# Connections.net
KiCad netlist of a schematic drawn in EAGLE
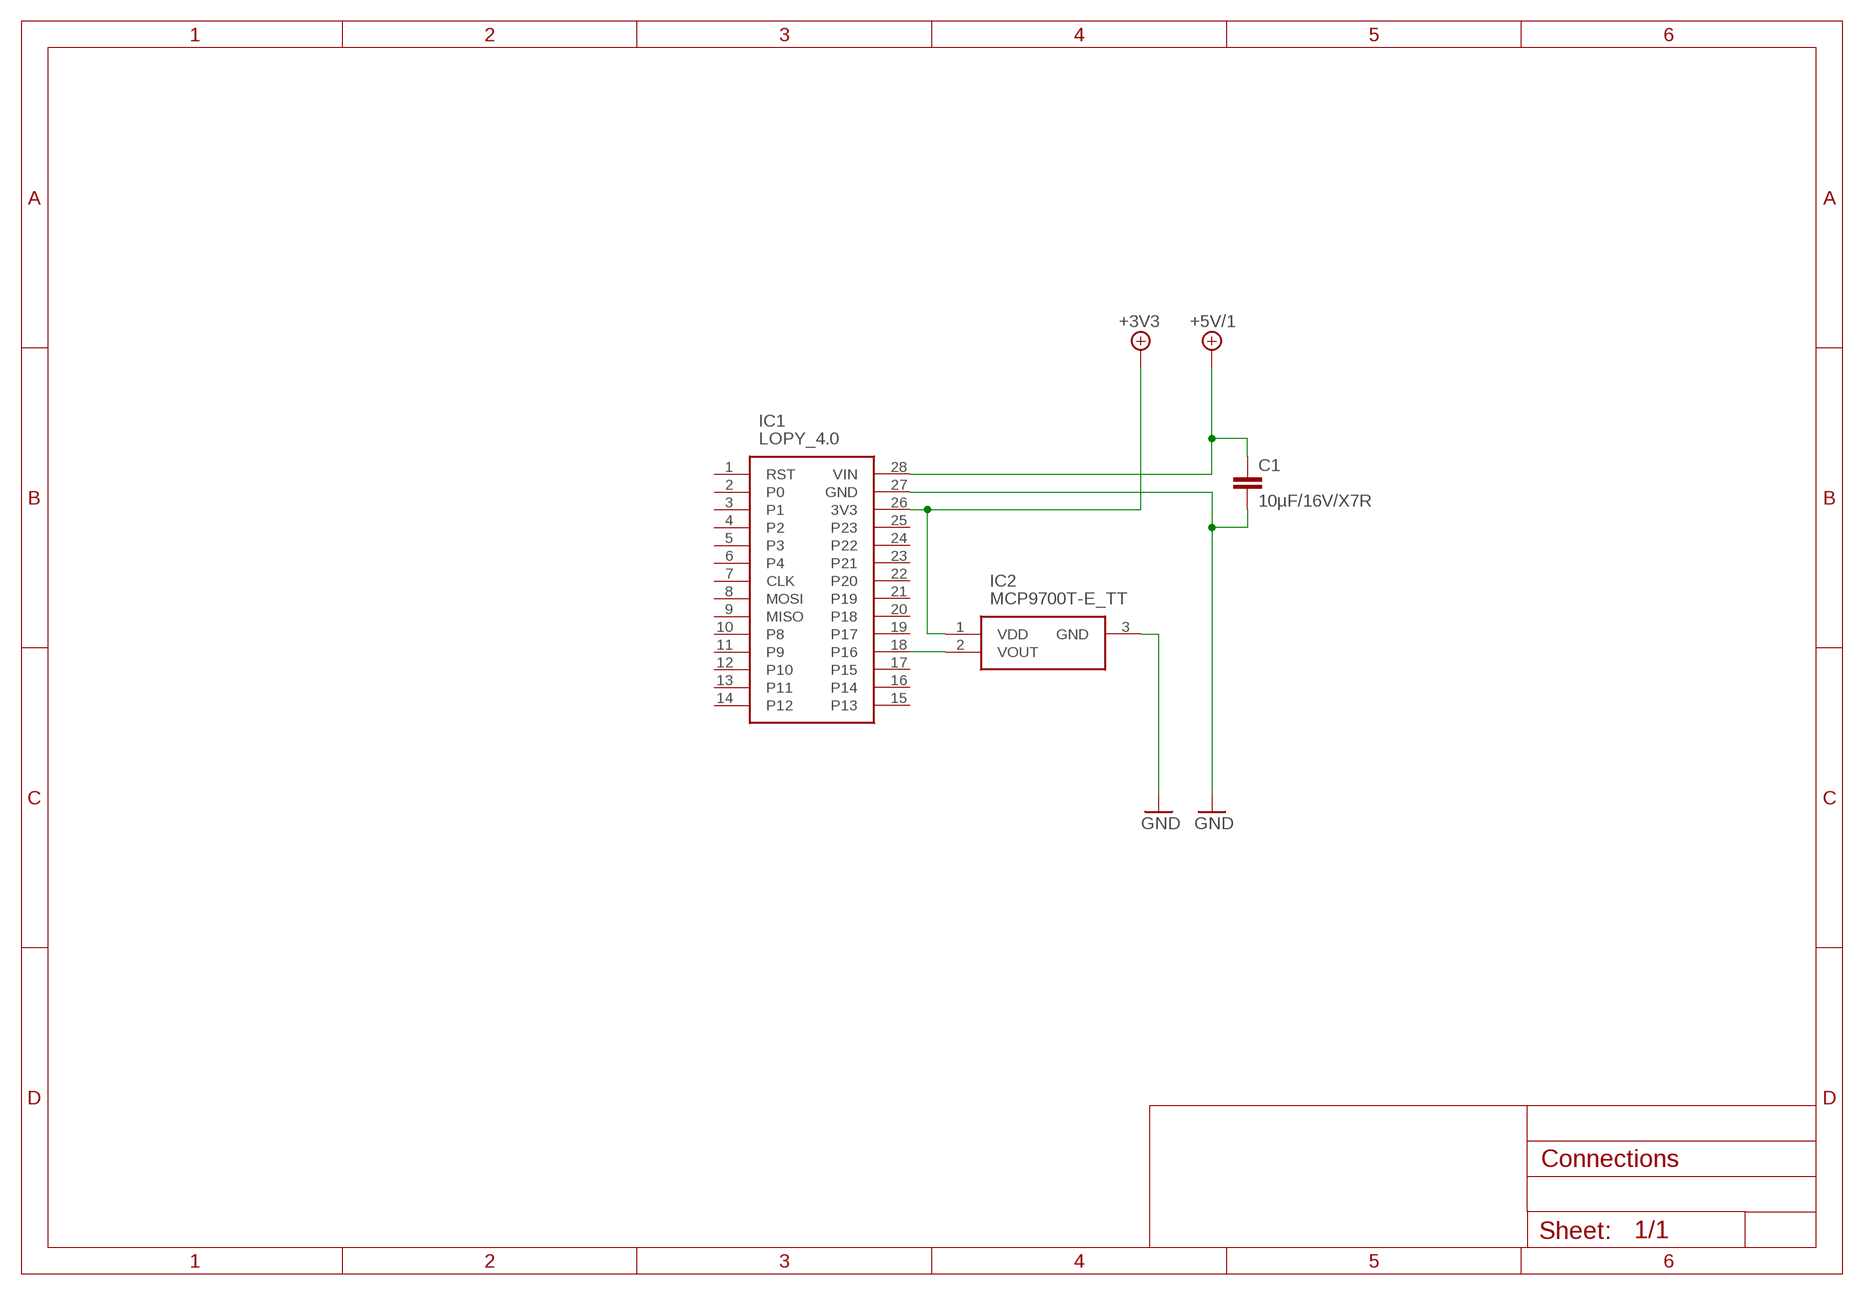
[diagram p0: schematic, sheet 1]

(export (version "E")
  (design (tool "Eeschema 10.0.6"))
  (components
    (comp (ref "C1")
      (value "10µF/16V/X7R")
      (footprint "eagle-import:C0603")
      (libsource (lib "eagle-import") (part "C-EUC0603"))
    )
    (comp (ref "IC1")
      (value "LOPY_4.0")
      (footprint "eagle-import:LOPY40")
      (fields (field (name "ARROW_PART_NUMBER") "LoPy 4.0") (field (name "MOUSER_PART_NUMBER") "365-LOPY4"))
      (libsource (lib "eagle-import") (part "LOPY_4.0"))
    )
    (comp (ref "IC2")
      (value "MCP9700T-E_TT")
      (footprint "eagle-import:SOT95P237X112-3N")
      (fields
        (field (name "ARROW_PART_NUMBER") "MCP9700T-E/TT")
        (field (name "MOUSER_PART_NUMBER") "579-MCP9700T-E/TT")
      )
      (libsource (lib "eagle-import") (part "MCP9700T-E_TT"))
    )
  )
  (nets
    (net (code "1") (name "+3V3") (class "Default")
      (node (ref "IC1") (pin "26") (pinfunction "3V3_26") (pintype "bidirectional"))
      (node (ref "IC2") (pin "1") (pinfunction "VDD_1") (pintype "bidirectional"))
    )
    (net (code "2") (name "+5V{slash}1") (class "Default")
      (node (ref "C1") (pin "1") (pinfunction "1_1") (pintype "passive"))
      (node (ref "IC1") (pin "28") (pinfunction "VIN_28") (pintype "bidirectional"))
    )
    (net (code "3") (name "GND") (class "Default")
      (node (ref "C1") (pin "2") (pinfunction "2_2") (pintype "passive"))
      (node (ref "IC1") (pin "27") (pinfunction "GND_27") (pintype "bidirectional"))
      (node (ref "IC2") (pin "3") (pinfunction "GND_3") (pintype "bidirectional"))
    )
    (net (code "4") (name "Net-(IC1-P16)") (class "Default")
      (node (ref "IC1") (pin "18") (pinfunction "P16_18") (pintype "bidirectional"))
      (node (ref "IC2") (pin "2") (pinfunction "VOUT_2") (pintype "bidirectional"))
    )
    (net (code "5") (name "unconnected-(IC1-CLK-Pad7)") (class "Default")
      (node (ref "IC1") (pin "7") (pinfunction "CLK_7") (pintype "bidirectional"))
    )
    (net (code "6") (name "unconnected-(IC1-MISO-Pad9)") (class "Default")
      (node (ref "IC1") (pin "9") (pinfunction "MISO_9") (pintype "bidirectional"))
    )
    (net (code "7") (name "unconnected-(IC1-MOSI-Pad8)") (class "Default")
      (node (ref "IC1") (pin "8") (pinfunction "MOSI_8") (pintype "bidirectional"))
    )
    (net (code "8") (name "unconnected-(IC1-P0-Pad2)") (class "Default")
      (node (ref "IC1") (pin "2") (pinfunction "P0_2") (pintype "bidirectional"))
    )
    (net (code "9") (name "unconnected-(IC1-P1-Pad3)") (class "Default")
      (node (ref "IC1") (pin "3") (pinfunction "P1_3") (pintype "bidirectional"))
    )
    (net (code "10") (name "unconnected-(IC1-P2-Pad4)") (class "Default")
      (node (ref "IC1") (pin "4") (pinfunction "P2_4") (pintype "bidirectional"))
    )
    (net (code "11") (name "unconnected-(IC1-P3-Pad5)") (class "Default")
      (node (ref "IC1") (pin "5") (pinfunction "P3_5") (pintype "bidirectional"))
    )
    (net (code "12") (name "unconnected-(IC1-P4-Pad6)") (class "Default")
      (node (ref "IC1") (pin "6") (pinfunction "P4_6") (pintype "bidirectional"))
    )
    (net (code "13") (name "unconnected-(IC1-P8-Pad10)") (class "Default")
      (node (ref "IC1") (pin "10") (pinfunction "P8_10") (pintype "bidirectional"))
    )
    (net (code "14") (name "unconnected-(IC1-P9-Pad11)") (class "Default")
      (node (ref "IC1") (pin "11") (pinfunction "P9_11") (pintype "bidirectional"))
    )
    (net (code "15") (name "unconnected-(IC1-P10-Pad12)") (class "Default")
      (node (ref "IC1") (pin "12") (pinfunction "P10_12") (pintype "bidirectional"))
    )
    (net (code "16") (name "unconnected-(IC1-P11-Pad13)") (class "Default")
      (node (ref "IC1") (pin "13") (pinfunction "P11_13") (pintype "bidirectional"))
    )
    (net (code "17") (name "unconnected-(IC1-P12-Pad14)") (class "Default")
      (node (ref "IC1") (pin "14") (pinfunction "P12_14") (pintype "bidirectional"))
    )
    (net (code "18") (name "unconnected-(IC1-P13-Pad15)") (class "Default")
      (node (ref "IC1") (pin "15") (pinfunction "P13_15") (pintype "bidirectional"))
    )
    (net (code "19") (name "unconnected-(IC1-P14-Pad16)") (class "Default")
      (node (ref "IC1") (pin "16") (pinfunction "P14_16") (pintype "bidirectional"))
    )
    (net (code "20") (name "unconnected-(IC1-P15-Pad17)") (class "Default")
      (node (ref "IC1") (pin "17") (pinfunction "P15_17") (pintype "bidirectional"))
    )
    (net (code "21") (name "unconnected-(IC1-P17-Pad19)") (class "Default")
      (node (ref "IC1") (pin "19") (pinfunction "P17_19") (pintype "bidirectional"))
    )
    (net (code "22") (name "unconnected-(IC1-P18-Pad20)") (class "Default")
      (node (ref "IC1") (pin "20") (pinfunction "P18_20") (pintype "bidirectional"))
    )
    (net (code "23") (name "unconnected-(IC1-P19-Pad21)") (class "Default")
      (node (ref "IC1") (pin "21") (pinfunction "P19_21") (pintype "bidirectional"))
    )
    (net (code "24") (name "unconnected-(IC1-P20-Pad22)") (class "Default")
      (node (ref "IC1") (pin "22") (pinfunction "P20_22") (pintype "bidirectional"))
    )
    (net (code "25") (name "unconnected-(IC1-P21-Pad23)") (class "Default")
      (node (ref "IC1") (pin "23") (pinfunction "P21_23") (pintype "bidirectional"))
    )
    (net (code "26") (name "unconnected-(IC1-P22-Pad24)") (class "Default")
      (node (ref "IC1") (pin "24") (pinfunction "P22_24") (pintype "bidirectional"))
    )
    (net (code "27") (name "unconnected-(IC1-P23-Pad25)") (class "Default")
      (node (ref "IC1") (pin "25") (pinfunction "P23_25") (pintype "bidirectional"))
    )
    (net (code "28") (name "unconnected-(IC1-RST-Pad1)") (class "Default")
      (node (ref "IC1") (pin "1") (pinfunction "RST_1") (pintype "bidirectional"))
    )
  )
)
